# narsil.net
KiCad netlist of a schematic drawn in EAGLE
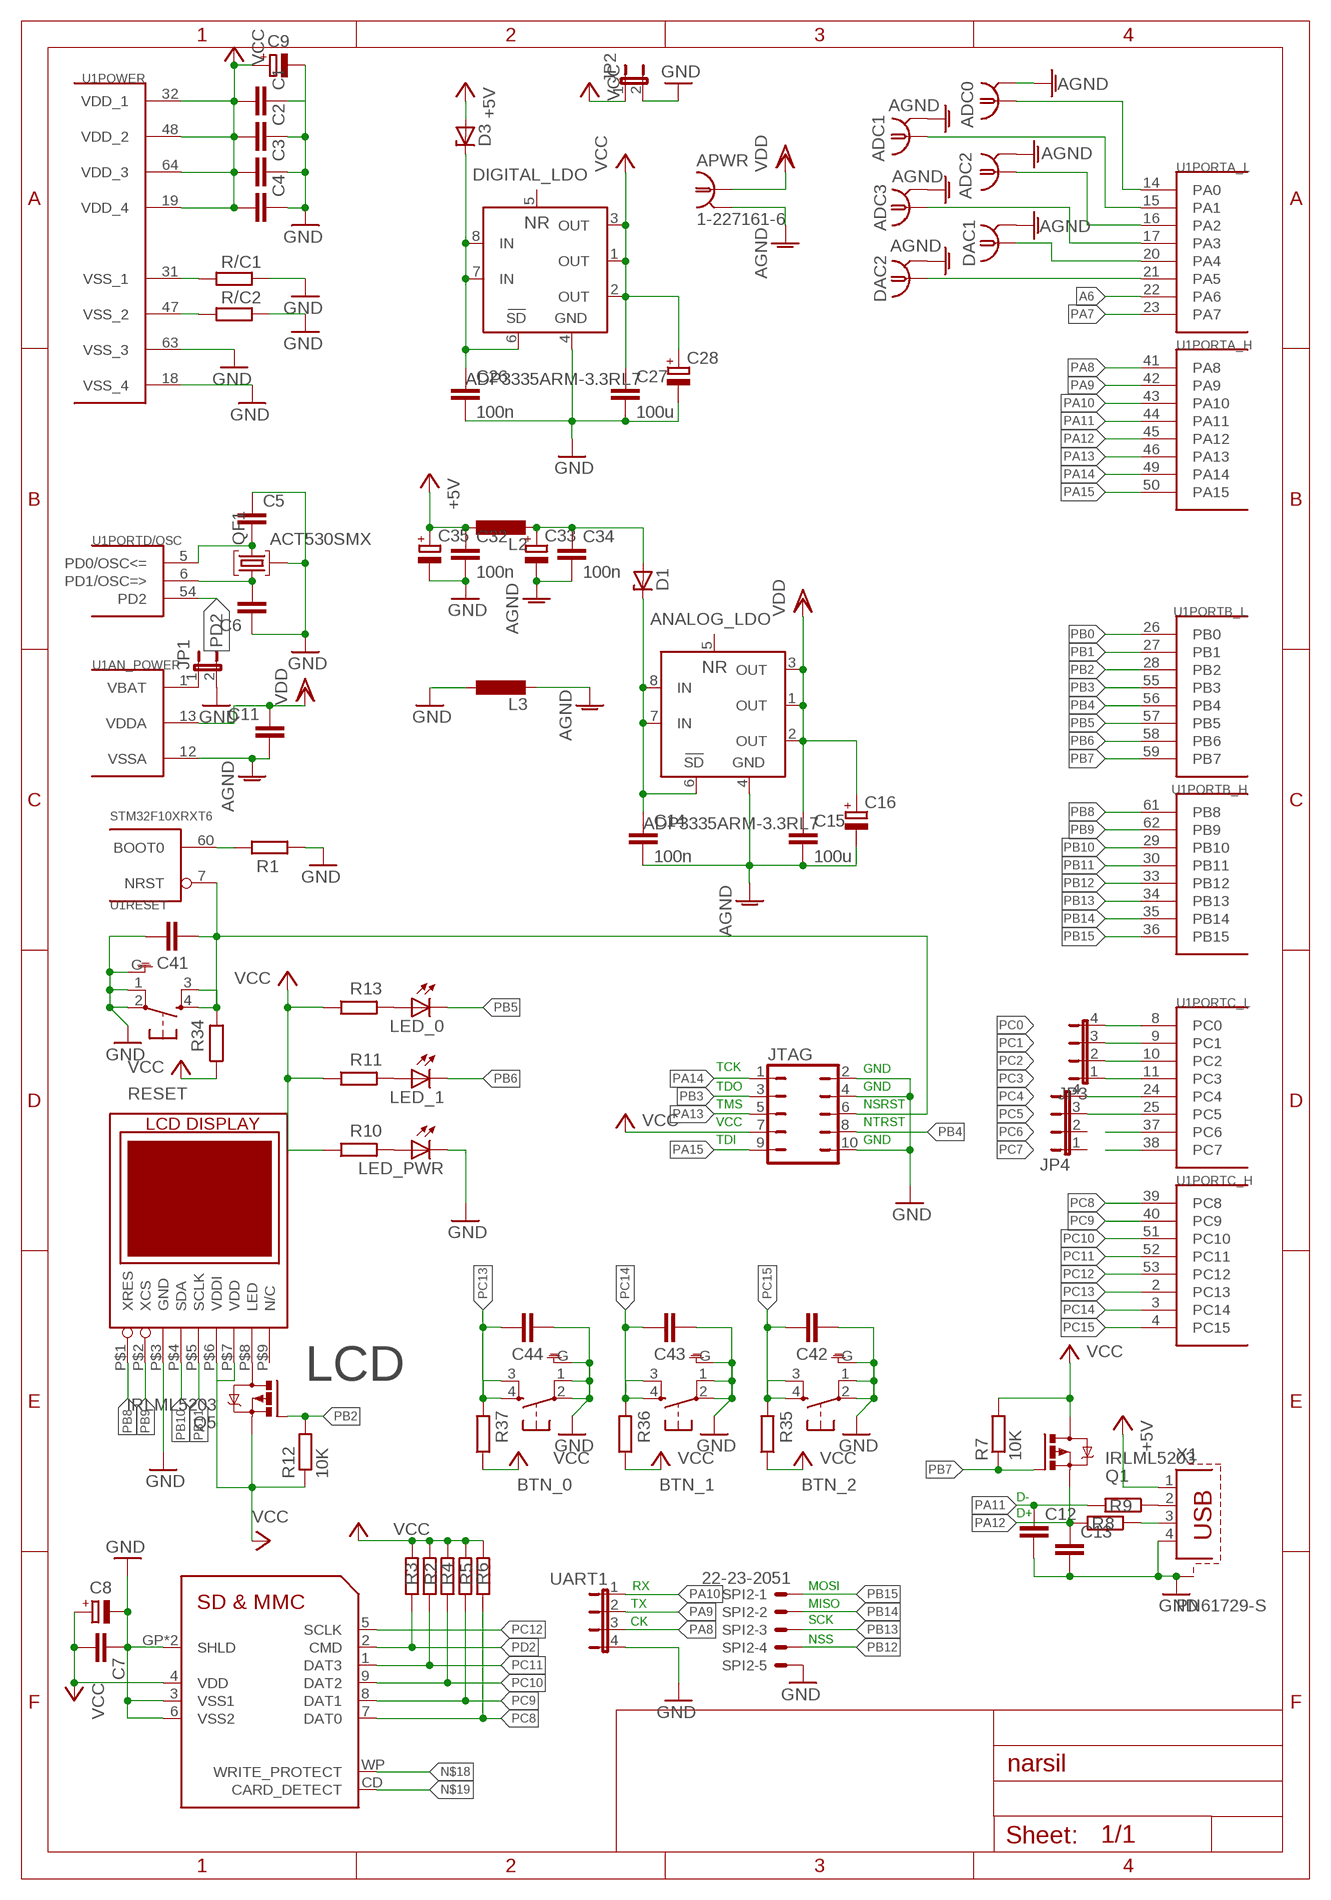
[diagram p0: schematic, sheet 1]

(export (version "E")
  (design (tool "Eeschema 10.0.6"))
  (components
    (comp (ref "ADC0")
      (value "1-227161-6")
      (footprint "eagle-import:AMP_227161")
      (fields (field (name "MF") "TYCO ELECTRONICS"))
      (libsource (lib "eagle-import") (part "?2271611--6"))
    )
    (comp (ref "ADC1")
      (value "1-227161-6")
      (footprint "eagle-import:AMP_227161")
      (fields (field (name "MF") "TYCO ELECTRONICS"))
      (libsource (lib "eagle-import") (part "?2271611--6"))
    )
    (comp (ref "ADC2")
      (value "1-227161-6")
      (footprint "eagle-import:AMP_227161")
      (fields (field (name "MF") "TYCO ELECTRONICS"))
      (libsource (lib "eagle-import") (part "?2271611--6"))
    )
    (comp (ref "ADC3")
      (value "1-227161-6")
      (footprint "eagle-import:AMP_227161")
      (fields
        (field (name "MF") "TYCO ELECTRONICS")
        (field (name "MF_1") "TYCO ELECTRONICS")
        (field (name "MPN") "1-227161-6")
        (field (name "OC_FARNELL") "unknown")
        (field (name "OC_NEWARK") "09H7854")
      )
      (libsource (lib "eagle-import") (part "?2271611--6"))
    )
    (comp (ref "ANALOG_LDO")
      (value "ADP3335ARM-3.3RL7")
      (footprint "eagle-import:MSOP08")
      (libsource (lib "eagle-import") (part "ADP3335ARM-3.3RL7"))
    )
    (comp (ref "APWR")
      (value "1-227161-6")
      (footprint "eagle-import:AMP_227161")
      (fields (field (name "MF") "TYCO ELECTRONICS"))
      (libsource (lib "eagle-import") (part "?2271611--6"))
    )
    (comp (ref "BTN_0")
      (value "10-XXG")
      (footprint "eagle-import:B3F-10XXG")
      (libsource (lib "eagle-import") (part "10-XXG"))
    )
    (comp (ref "BTN_1")
      (value "10-XXG")
      (footprint "eagle-import:B3F-10XXG")
      (libsource (lib "eagle-import") (part "10-XXG"))
    )
    (comp (ref "BTN_2")
      (value "10-XXG")
      (footprint "eagle-import:B3F-10XXG")
      (libsource (lib "eagle-import") (part "10-XXG"))
    )
    (comp (ref "C1")
      (value "C-EUC0805")
      (footprint "eagle-import:C0805")
      (libsource (lib "eagle-import") (part "resistor_C-EUC0805"))
    )
    (comp (ref "C2")
      (value "C-EUC0805")
      (footprint "eagle-import:C0805")
      (libsource (lib "eagle-import") (part "resistor_C-EUC0805"))
    )
    (comp (ref "C3")
      (value "C-EUC0805")
      (footprint "eagle-import:C0805")
      (libsource (lib "eagle-import") (part "resistor_C-EUC0805"))
    )
    (comp (ref "C4")
      (value "C-EUC0805")
      (footprint "eagle-import:C0805")
      (libsource (lib "eagle-import") (part "resistor_C-EUC0805"))
    )
    (comp (ref "C5")
      (value "C-EUC0805")
      (footprint "eagle-import:C0805")
      (libsource (lib "eagle-import") (part "resistor_C-EUC0805"))
    )
    (comp (ref "C6")
      (value "C-EUC0805")
      (footprint "eagle-import:C0805")
      (libsource (lib "eagle-import") (part "resistor_C-EUC0805"))
    )
    (comp (ref "C7")
      (value "C-EUC0805")
      (footprint "eagle-import:C0805")
      (libsource (lib "eagle-import") (part "resistor_C-EUC0805"))
    )
    (comp (ref "C8")
      (value "CPOL-EUSMCA")
      (footprint "eagle-import:SMC_A")
      (libsource (lib "eagle-import") (part "CPOL-EUSMCA"))
    )
    (comp (ref "C9")
      (value "CPOL-EUSMCA")
      (footprint "eagle-import:SMC_A")
      (libsource (lib "eagle-import") (part "CPOL-EUSMCA"))
    )
    (comp (ref "C11")
      (value "C-EUC0805")
      (footprint "eagle-import:C0805")
      (libsource (lib "eagle-import") (part "resistor_C-EUC0805"))
    )
    (comp (ref "C12")
      (value "C-EUC0805")
      (footprint "eagle-import:C0805")
      (libsource (lib "eagle-import") (part "resistor_C-EUC0805"))
    )
    (comp (ref "C13")
      (value "C-EUC0805")
      (footprint "eagle-import:C0805")
      (libsource (lib "eagle-import") (part "resistor_C-EUC0805"))
    )
    (comp (ref "C14")
      (value "100n")
      (footprint "eagle-import:C0805")
      (libsource (lib "eagle-import") (part "C-EUC0805"))
    )
    (comp (ref "C15")
      (value "100u")
      (footprint "eagle-import:C0805")
      (libsource (lib "eagle-import") (part "C-EUC0805"))
    )
    (comp (ref "C16")
      (value "CPOL-EUSMCA")
      (footprint "eagle-import:SMC_A")
      (libsource (lib "eagle-import") (part "CPOL-EUSMCA"))
    )
    (comp (ref "C26")
      (value "100n")
      (footprint "eagle-import:C0805")
      (libsource (lib "eagle-import") (part "C-EUC0805"))
    )
    (comp (ref "C27")
      (value "100u")
      (footprint "eagle-import:C0805")
      (libsource (lib "eagle-import") (part "C-EUC0805"))
    )
    (comp (ref "C28")
      (value "CPOL-EUSMCA")
      (footprint "eagle-import:SMC_A")
      (libsource (lib "eagle-import") (part "CPOL-EUSMCA"))
    )
    (comp (ref "C32")
      (value "100n")
      (footprint "eagle-import:C0805")
      (libsource (lib "eagle-import") (part "resistor_C-EUC0805"))
    )
    (comp (ref "C33")
      (value "CPOL-EUSMCA")
      (footprint "eagle-import:SMC_A")
      (libsource (lib "eagle-import") (part "CPOL-EUSMCA"))
    )
    (comp (ref "C34")
      (value "100n")
      (footprint "eagle-import:C0805")
      (libsource (lib "eagle-import") (part "resistor_C-EUC0805"))
    )
    (comp (ref "C35")
      (value "CPOL-EUSMCA")
      (footprint "eagle-import:SMC_A")
      (libsource (lib "eagle-import") (part "CPOL-EUSMCA"))
    )
    (comp (ref "C41")
      (value "C-EUC0805")
      (footprint "eagle-import:C0805")
      (libsource (lib "eagle-import") (part "resistor_C-EUC0805"))
    )
    (comp (ref "C42")
      (value "C-EUC0805")
      (footprint "eagle-import:C0805")
      (libsource (lib "eagle-import") (part "resistor_C-EUC0805"))
    )
    (comp (ref "C43")
      (value "C-EUC0805")
      (footprint "eagle-import:C0805")
      (libsource (lib "eagle-import") (part "resistor_C-EUC0805"))
    )
    (comp (ref "C44")
      (value "C-EUC0805")
      (footprint "eagle-import:C0805")
      (libsource (lib "eagle-import") (part "resistor_C-EUC0805"))
    )
    (comp (ref "D1")
      (value "ZENER-DIODESMB")
      (footprint "eagle-import:SMB")
      (libsource (lib "eagle-import") (part "ZENER-DIODESMB"))
    )
    (comp (ref "D3")
      (value "ZENER-DIODESMB")
      (footprint "eagle-import:SMB")
      (libsource (lib "eagle-import") (part "ZENER-DIODESMB"))
    )
    (comp (ref "DAC1")
      (value "1-227161-6")
      (footprint "eagle-import:AMP_227161")
      (fields (field (name "MF") "TYCO ELECTRONICS"))
      (libsource (lib "eagle-import") (part "?2271611--6"))
    )
    (comp (ref "DAC2")
      (value "1-227161-6")
      (footprint "eagle-import:AMP_227161")
      (fields (field (name "MF") "TYCO ELECTRONICS"))
      (libsource (lib "eagle-import") (part "?2271611--6"))
    )
    (comp (ref "DIGITAL_LDO")
      (value "ADP3335ARM-3.3RL7")
      (footprint "eagle-import:MSOP08")
      (libsource (lib "eagle-import") (part "ADP3335ARM-3.3RL7"))
    )
    (comp (ref "JP1")
      (value "JP1E")
      (footprint "eagle-import:JP1")
      (libsource (lib "eagle-import") (part "JP1E"))
    )
    (comp (ref "JP2")
      (value "JP1E")
      (footprint "eagle-import:JP1")
      (libsource (lib "eagle-import") (part "JP1E"))
    )
    (comp (ref "JP3")
      (value "JP4E")
      (footprint "eagle-import:JP4")
      (libsource (lib "eagle-import") (part "JP4E"))
    )
    (comp (ref "JP4")
      (value "JP4E")
      (footprint "eagle-import:JP4")
      (libsource (lib "eagle-import") (part "JP4E"))
    )
    (comp (ref "JTAG")
      (value "JP5Q")
      (footprint "eagle-import:JP5Q")
      (libsource (lib "eagle-import") (part "JP5Q"))
    )
    (comp (ref "L2")
      (value "L-EUL1206")
      (footprint "eagle-import:R1206")
      (libsource (lib "eagle-import") (part "L-EUL1206"))
    )
    (comp (ref "L3")
      (value "L-EUL1206")
      (footprint "eagle-import:R1206")
      (libsource (lib "eagle-import") (part "L-EUL1206"))
    )
    (comp (ref "LED_0")
      (value "LEDSMT1206")
      (footprint "eagle-import:1206")
      (libsource (lib "eagle-import") (part "LEDSMT1206"))
    )
    (comp (ref "LED_1")
      (value "LEDSMT1206")
      (footprint "eagle-import:1206")
      (libsource (lib "eagle-import") (part "LEDSMT1206"))
    )
    (comp (ref "LED_PWR")
      (value "LEDSMT1206")
      (footprint "eagle-import:1206")
      (libsource (lib "eagle-import") (part "LEDSMT1206"))
    )
    (comp (ref "Q1")
      (value "IRLML5203")
      (footprint "eagle-import:MICRO3")
      (libsource (lib "eagle-import") (part "IRLML5203"))
    )
    (comp (ref "Q5")
      (value "IRLML5203")
      (footprint "eagle-import:MICRO3")
      (libsource (lib "eagle-import") (part "IRLML5203"))
    )
    (comp (ref "QF1")
      (value "ACT530SMX")
      (footprint "eagle-import:ACT530SMX")
      (libsource (lib "eagle-import") (part "ACT530SMX"))
    )
    (comp (ref "R/C1")
      (value "R-EU_M0805")
      (footprint "eagle-import:M0805")
      (libsource (lib "eagle-import") (part "R-EU_M0805"))
    )
    (comp (ref "R/C2")
      (value "R-EU_M0805")
      (footprint "eagle-import:M0805")
      (libsource (lib "eagle-import") (part "R-EU_M0805"))
    )
    (comp (ref "R1")
      (value "5k")
      (footprint "eagle-import:M0805")
      (libsource (lib "eagle-import") (part "R-EU_M0805"))
    )
    (comp (ref "R2")
      (value "47k")
      (footprint "eagle-import:M0805")
      (libsource (lib "eagle-import") (part "R-EU_M0805"))
    )
    (comp (ref "R3")
      (value "47k")
      (footprint "eagle-import:M0805")
      (libsource (lib "eagle-import") (part "R-EU_M0805"))
    )
    (comp (ref "R4")
      (value "47k")
      (footprint "eagle-import:M0805")
      (libsource (lib "eagle-import") (part "R-EU_M0805"))
    )
    (comp (ref "R5")
      (value "47k")
      (footprint "eagle-import:M0805")
      (libsource (lib "eagle-import") (part "R-EU_M0805"))
    )
    (comp (ref "R6")
      (value "47k")
      (footprint "eagle-import:M0805")
      (libsource (lib "eagle-import") (part "R-EU_M0805"))
    )
    (comp (ref "R7")
      (value "10K")
      (footprint "eagle-import:M0805")
      (libsource (lib "eagle-import") (part "R-EU_M0805"))
    )
    (comp (ref "R8")
      (value "47k")
      (footprint "eagle-import:M0805")
      (libsource (lib "eagle-import") (part "R-EU_M0805"))
    )
    (comp (ref "R9")
      (value "47k")
      (footprint "eagle-import:M0805")
      (libsource (lib "eagle-import") (part "R-EU_M0805"))
    )
    (comp (ref "R10")
      (value "5k")
      (footprint "eagle-import:M0805")
      (libsource (lib "eagle-import") (part "R-EU_M0805"))
    )
    (comp (ref "R11")
      (value "5k")
      (footprint "eagle-import:M0805")
      (libsource (lib "eagle-import") (part "R-EU_M0805"))
    )
    (comp (ref "R12")
      (value "10K")
      (footprint "eagle-import:M0805")
      (libsource (lib "eagle-import") (part "R-EU_M0805"))
    )
    (comp (ref "R13")
      (value "5k")
      (footprint "eagle-import:M0805")
      (libsource (lib "eagle-import") (part "R-EU_M0805"))
    )
    (comp (ref "R34")
      (value "5k")
      (footprint "eagle-import:M0805")
      (libsource (lib "eagle-import") (part "R-EU_M0805"))
    )
    (comp (ref "R35")
      (value "5k")
      (footprint "eagle-import:M0805")
      (libsource (lib "eagle-import") (part "R-EU_M0805"))
    )
    (comp (ref "R36")
      (value "5k")
      (footprint "eagle-import:M0805")
      (libsource (lib "eagle-import") (part "R-EU_M0805"))
    )
    (comp (ref "R37")
      (value "5k")
      (footprint "eagle-import:M0805")
      (libsource (lib "eagle-import") (part "R-EU_M0805"))
    )
    (comp (ref "RESET")
      (value "10-XXG")
      (footprint "eagle-import:B3F-10XXG")
      (libsource (lib "eagle-import") (part "10-XXG"))
    )
    (comp (ref "SPI2")
      (value "22-23-2051")
      (footprint "eagle-import:22-23-2051")
      (fields (field (name "MF") "MOLEX"))
      (libsource (lib "eagle-import") (part "22-23-2051"))
    )
    (comp (ref "U$1")
      (value "SD-RSMT-2-MQ")
      (footprint "eagle-import:SD-RSMT-2-MQ")
      (libsource (lib "eagle-import") (part "SD-RSMT-2-MQ"))
    )
    (comp (ref "U$2")
      (value "LCD")
      (footprint "eagle-import:LCD_NOKIA1100")
      (libsource (lib "eagle-import") (part "LCD"))
    )
    (comp (ref "U1")
      (value "STM32F10XRXT6")
      (footprint "eagle-import:TQFP64")
      (libsource (lib "eagle-import") (part "STM32F10XRXT6"))
    )
    (comp (ref "UART1")
      (value "JP4E")
      (footprint "eagle-import:JP4")
      (libsource (lib "eagle-import") (part "JP4E"))
    )
    (comp (ref "X1")
      (value "PN61729-S")
      (footprint "eagle-import:PN61729-S")
      (libsource (lib "eagle-import") (part "PN61729-S"))
    )
  )
  (nets
    (net (code "1") (name "+5V") (class "Default")
      (node (ref "C32") (pin "1") (pinfunction "1_1") (pintype "passive"))
      (node (ref "C35") (pin "+") (pinfunction "+_+") (pintype "passive"))
      (node (ref "D3") (pin "A") (pinfunction "A_A") (pintype "passive"))
      (node (ref "L2") (pin "1") (pinfunction "1_1") (pintype "passive"))
      (node (ref "X1") (pin "1") (pinfunction "1_1") (pintype "passive"))
    )
    (net (code "2") (name "A6") (class "Default")
      (node (ref "U1") (pin "22") (pinfunction "PA6_22") (pintype "bidirectional"))
    )
    (net (code "3") (name "AGND") (class "Default")
      (node (ref "ADC0") (pin "2") (pinfunction "GND_2") (pintype "power_in"))
      (node (ref "ADC1") (pin "2") (pinfunction "GND_2") (pintype "power_in"))
      (node (ref "ADC2") (pin "2") (pinfunction "GND_2") (pintype "power_in"))
      (node (ref "ADC3") (pin "2") (pinfunction "GND_2") (pintype "power_in"))
      (node (ref "ANALOG_LDO") (pin "4") (pinfunction "GND_4") (pintype "power_in"))
      (node (ref "APWR") (pin "2") (pinfunction "GND_2") (pintype "power_in"))
      (node (ref "C11") (pin "2") (pinfunction "2_2") (pintype "passive"))
      (node (ref "C14") (pin "2") (pinfunction "2_2") (pintype "passive"))
      (node (ref "C15") (pin "2") (pinfunction "2_2") (pintype "passive"))
      (node (ref "C16") (pin "-") (pinfunction "-_-") (pintype "passive"))
      (node (ref "C33") (pin "-") (pinfunction "-_-") (pintype "passive"))
      (node (ref "C34") (pin "2") (pinfunction "2_2") (pintype "passive"))
      (node (ref "DAC1") (pin "2") (pinfunction "GND_2") (pintype "power_in"))
      (node (ref "DAC2") (pin "2") (pinfunction "GND_2") (pintype "power_in"))
      (node (ref "L3") (pin "2") (pinfunction "2_2") (pintype "passive"))
      (node (ref "U1") (pin "12") (pinfunction "VSSA_12") (pintype "power_in"))
    )
    (net (code "4") (name "GND") (class "Default")
      (node (ref "BTN_0") (pin "1") (pinfunction "P1_1") (pintype "passive"))
      (node (ref "BTN_0") (pin "2") (pinfunction "P_2") (pintype "passive"))
      (node (ref "BTN_0") (pin "G") (pinfunction "GND_G") (pintype "power_in"))
      (node (ref "BTN_1") (pin "1") (pinfunction "P1_1") (pintype "passive"))
      (node (ref "BTN_1") (pin "2") (pinfunction "P_2") (pintype "passive"))
      (node (ref "BTN_1") (pin "G") (pinfunction "GND_G") (pintype "power_in"))
      (node (ref "BTN_2") (pin "1") (pinfunction "P1_1") (pintype "passive"))
      (node (ref "BTN_2") (pin "2") (pinfunction "P_2") (pintype "passive"))
      (node (ref "BTN_2") (pin "G") (pinfunction "GND_G") (pintype "power_in"))
      (node (ref "C1") (pin "1") (pinfunction "1_1") (pintype "passive"))
      (node (ref "C12") (pin "2") (pinfunction "2_2") (pintype "passive"))
      (node (ref "C13") (pin "2") (pinfunction "2_2") (pintype "passive"))
      (node (ref "C2") (pin "1") (pinfunction "1_1") (pintype "passive"))
      (node (ref "C26") (pin "2") (pinfunction "2_2") (pintype "passive"))
      (node (ref "C27") (pin "2") (pinfunction "2_2") (pintype "passive"))
      (node (ref "C28") (pin "-") (pinfunction "-_-") (pintype "passive"))
      (node (ref "C3") (pin "1") (pinfunction "1_1") (pintype "passive"))
      (node (ref "C32") (pin "2") (pinfunction "2_2") (pintype "passive"))
      (node (ref "C35") (pin "-") (pinfunction "-_-") (pintype "passive"))
      (node (ref "C4") (pin "1") (pinfunction "1_1") (pintype "passive"))
      (node (ref "C41") (pin "1") (pinfunction "1_1") (pintype "passive"))
      (node (ref "C42") (pin "1") (pinfunction "1_1") (pintype "passive"))
      (node (ref "C43") (pin "1") (pinfunction "1_1") (pintype "passive"))
      (node (ref "C44") (pin "1") (pinfunction "1_1") (pintype "passive"))
      (node (ref "C5") (pin "1") (pinfunction "1_1") (pintype "passive"))
      (node (ref "C6") (pin "1") (pinfunction "1_1") (pintype "passive"))
      (node (ref "C7") (pin "1") (pinfunction "1_1") (pintype "passive"))
      (node (ref "C8") (pin "-") (pinfunction "-_-") (pintype "passive"))
      (node (ref "C9") (pin "-") (pinfunction "-_-") (pintype "passive"))
      (node (ref "DIGITAL_LDO") (pin "4") (pinfunction "GND_4") (pintype "power_in"))
      (node (ref "JP1") (pin "2") (pinfunction "2_2") (pintype "passive"))
      (node (ref "JP2") (pin "2") (pinfunction "2_2") (pintype "passive"))
      (node (ref "JTAG") (pin "10") (pinfunction "10_10") (pintype "passive"))
      (node (ref "JTAG") (pin "2") (pinfunction "2_2") (pintype "passive"))
      (node (ref "JTAG") (pin "4") (pinfunction "4_4") (pintype "passive"))
      (node (ref "L3") (pin "1") (pinfunction "1_1") (pintype "passive"))
      (node (ref "LED_PWR") (pin "C") (pinfunction "C_C") (pintype "passive"))
      (node (ref "QF1") (pin "S$1") (pinfunction "2_S$1") (pintype "passive"))
      (node (ref "QF1") (pin "S$2") (pinfunction "2_S$2") (pintype "passive"))
      (node (ref "R/C1") (pin "1") (pinfunction "1_1") (pintype "passive"))
      (node (ref "R/C2") (pin "1") (pinfunction "1_1") (pintype "passive"))
      (node (ref "R1") (pin "1") (pinfunction "1_1") (pintype "passive"))
      (node (ref "RESET") (pin "1") (pinfunction "P1_1") (pintype "passive"))
      (node (ref "RESET") (pin "2") (pinfunction "P_2") (pintype "passive"))
      (node (ref "RESET") (pin "G") (pinfunction "GND_G") (pintype "power_in"))
      (node (ref "SPI2") (pin "5") (pinfunction "S_5") (pintype "passive"))
      (node (ref "U$1") (pin "3") (pinfunction "VSS1_3") (pintype "power_in"))
      (node (ref "U$1") (pin "6") (pinfunction "VSS2_6") (pintype "power_in"))
      (node (ref "U$1") (pin "GP") (pinfunction "SHLD_GP") (pintype "power_in"))
      (node (ref "U$1") (pin "GP2") (pinfunction "SHLD_GP2") (pintype "power_in"))
      (node (ref "U$2") (pin "P$3") (pinfunction "GND_P$3") (pintype "power_in"))
      (node (ref "U1") (pin "18") (pinfunction "VSS_4_18") (pintype "power_in"))
      (node (ref "U1") (pin "63") (pinfunction "VSS_3_63") (pintype "power_in"))
      (node (ref "UART1") (pin "4") (pinfunction "4_4") (pintype "passive"))
      (node (ref "X1") (pin "4") (pinfunction "4_4") (pintype "passive"))
      (node (ref "X1") (pin "SHLD@1") (pinfunction "S1_SHLD@1") (pintype "passive"))
      (node (ref "X1") (pin "SHLD@2") (pinfunction "S1_SHLD@2") (pintype "passive"))
    )
    (net (code "5") (name "N$18") (class "Default")
      (node (ref "U$1") (pin "WP") (pinfunction "WRITE_PROTECT_WP") (pintype "passive"))
    )
    (net (code "6") (name "N$19") (class "Default")
      (node (ref "U$1") (pin "CD") (pinfunction "CARD_DETECT_CD") (pintype "passive"))
    )
    (net (code "7") (name "Net-(ANALOG_LDO-SD{slash})") (class "Default")
      (node (ref "ANALOG_LDO") (pin "6") (pinfunction "SD/_6") (pintype "input"))
      (node (ref "ANALOG_LDO") (pin "7") (pinfunction "IN_7") (pintype "input"))
      (node (ref "ANALOG_LDO") (pin "8") (pinfunction "IN_8") (pintype "input"))
      (node (ref "C14") (pin "1") (pinfunction "1_1") (pintype "passive"))
      (node (ref "D1") (pin "C") (pinfunction "C_C") (pintype "passive"))
    )
    (net (code "8") (name "Net-(C33-Pad+)") (class "Default")
      (node (ref "C33") (pin "+") (pinfunction "+_+") (pintype "passive"))
      (node (ref "C34") (pin "1") (pinfunction "1_1") (pintype "passive"))
      (node (ref "D1") (pin "A") (pinfunction "A_A") (pintype "passive"))
      (node (ref "L2") (pin "2") (pinfunction "2_2") (pintype "passive"))
    )
    (net (code "9") (name "Net-(DIGITAL_LDO-SD{slash})") (class "Default")
      (node (ref "C26") (pin "1") (pinfunction "1_1") (pintype "passive"))
      (node (ref "D3") (pin "C") (pinfunction "C_C") (pintype "passive"))
      (node (ref "DIGITAL_LDO") (pin "6") (pinfunction "SD/_6") (pintype "input"))
      (node (ref "DIGITAL_LDO") (pin "7") (pinfunction "IN_7") (pintype "input"))
      (node (ref "DIGITAL_LDO") (pin "8") (pinfunction "IN_8") (pintype "input"))
    )
    (net (code "10") (name "Net-(LED_0-PadA)") (class "Default")
      (node (ref "LED_0") (pin "A") (pinfunction "A_A") (pintype "passive"))
      (node (ref "R13") (pin "2") (pinfunction "2_2") (pintype "passive"))
    )
    (net (code "11") (name "Net-(LED_1-PadA)") (class "Default")
      (node (ref "LED_1") (pin "A") (pinfunction "A_A") (pintype "passive"))
      (node (ref "R11") (pin "2") (pinfunction "2_2") (pintype "passive"))
    )
    (net (code "12") (name "Net-(LED_PWR-PadA)") (class "Default")
      (node (ref "LED_PWR") (pin "A") (pinfunction "A_A") (pintype "passive"))
      (node (ref "R10") (pin "2") (pinfunction "2_2") (pintype "passive"))
    )
    (net (code "13") (name "Net-(Q5-D)") (class "Default")
      (node (ref "Q5") (pin "3") (pinfunction "D_3") (pintype "passive"))
      (node (ref "U$2") (pin "P$8") (pinfunction "LED_P$8") (pintype "power_in"))
    )
    (net (code "14") (name "Net-(QF1-1)") (class "Default")
      (node (ref "C6") (pin "2") (pinfunction "2_2") (pintype "passive"))
      (node (ref "QF1") (pin "P1") (pinfunction "1_P1") (pintype "passive"))
      (node (ref "U1") (pin "6") (pinfunction "PD1/OSC=>_6") (pintype "bidirectional"))
    )
    (net (code "15") (name "Net-(QF1-3)") (class "Default")
      (node (ref "C5") (pin "2") (pinfunction "2_2") (pintype "passive"))
      (node (ref "QF1") (pin "P2") (pinfunction "3_P2") (pintype "passive"))
      (node (ref "U1") (pin "5") (pinfunction "PD0/OSC<=_5") (pintype "bidirectional"))
    )
    (net (code "16") (name "Net-(R8-Pad1)") (class "Default")
      (node (ref "R8") (pin "1") (pinfunction "1_1") (pintype "passive"))
      (node (ref "X1") (pin "3") (pinfunction "3_3") (pintype "passive"))
    )
    (net (code "17") (name "Net-(R9-Pad1)") (class "Default")
      (node (ref "R9") (pin "1") (pinfunction "1_1") (pintype "passive"))
      (node (ref "X1") (pin "2") (pinfunction "2_2") (pintype "passive"))
    )
    (net (code "18") (name "Net-(RESET-S)") (class "Default")
      (node (ref "C41") (pin "2") (pinfunction "2_2") (pintype "passive"))
      (node (ref "JTAG") (pin "6") (pinfunction "6_6") (pintype "passive"))
      (node (ref "R34") (pin "2") (pinfunction "2_2") (pintype "passive"))
      (node (ref "RESET") (pin "3") (pinfunction "S1_3") (pintype "passive"))
      (node (ref "RESET") (pin "4") (pinfunction "S_4") (pintype "passive"))
      (node (ref "U1") (pin "7") (pinfunction "NRST_7") (pintype "input"))
    )
    (net (code "19") (name "Net-(U1A-VBAT)") (class "Default")
      (node (ref "JP1") (pin "1") (pinfunction "1_1") (pintype "passive"))
      (node (ref "U1") (pin "1") (pinfunction "VBAT_1") (pintype "power_in"))
    )
    (net (code "20") (name "Net-(U1C-PA0)") (class "Default")
      (node (ref "ADC0") (pin "1") (pinfunction "1_1") (pintype "passive"))
      (node (ref "U1") (pin "14") (pinfunction "PA0_14") (pintype "bidirectional"))
    )
    (net (code "21") (name "Net-(U1C-PA1)") (class "Default")
      (node (ref "ADC1") (pin "1") (pinfunction "1_1") (pintype "passive"))
      (node (ref "U1") (pin "15") (pinfunction "PA1_15") (pintype "bidirectional"))
    )
    (net (code "22") (name "Net-(U1C-PA2)") (class "Default")
      (node (ref "ADC2") (pin "1") (pinfunction "1_1") (pintype "passive"))
      (node (ref "U1") (pin "16") (pinfunction "PA2_16") (pintype "bidirectional"))
    )
    (net (code "23") (name "Net-(U1C-PA3)") (class "Default")
      (node (ref "ADC3") (pin "1") (pinfunction "1_1") (pintype "passive"))
      (node (ref "U1") (pin "17") (pinfunction "PA3_17") (pintype "bidirectional"))
    )
    (net (code "24") (name "Net-(U1C-PA4)") (class "Default")
      (node (ref "DAC1") (pin "1") (pinfunction "1_1") (pintype "passive"))
      (node (ref "U1") (pin "20") (pinfunction "PA4_20") (pintype "bidirectional"))
    )
    (net (code "25") (name "Net-(U1C-PA5)") (class "Default")
      (node (ref "DAC2") (pin "1") (pinfunction "1_1") (pintype "passive"))
      (node (ref "U1") (pin "21") (pinfunction "PA5_21") (pintype "bidirectional"))
    )
    (net (code "26") (name "Net-(U1I-VSS_1)") (class "Default")
      (node (ref "R/C1") (pin "2") (pinfunction "2_2") (pintype "passive"))
      (node (ref "U1") (pin "31") (pinfunction "VSS_1_31") (pintype "power_in"))
    )
    (net (code "27") (name "Net-(U1I-VSS_2)") (class "Default")
      (node (ref "R/C2") (pin "2") (pinfunction "2_2") (pintype "passive"))
      (node (ref "U1") (pin "47") (pinfunction "VSS_2_47") (pintype "power_in"))
    )
    (net (code "28") (name "Net-(U1J-BOOT0)") (class "Default")
      (node (ref "R1") (pin "2") (pinfunction "2_2") (pintype "passive"))
      (node (ref "U1") (pin "60") (pinfunction "BOOT0_60") (pintype "input"))
    )
    (net (code "29") (name "PA7") (class "Default")
      (node (ref "U1") (pin "23") (pinfunction "PA7_23") (pintype "bidirectional"))
    )
    (net (code "30") (name "PA8") (class "Default")
      (node (ref "U1") (pin "41") (pinfunction "PA8_41") (pintype "bidirectional"))
      (node (ref "UART1") (pin "3") (pinfunction "3_3") (pintype "passive"))
    )
    (net (code "31") (name "PA9") (class "Default")
      (node (ref "U1") (pin "42") (pinfunction "PA9_42") (pintype "bidirectional"))
      (node (ref "UART1") (pin "2") (pinfunction "2_2") (pintype "passive"))
    )
    (net (code "32") (name "PA10") (class "Default")
      (node (ref "U1") (pin "43") (pinfunction "PA10_43") (pintype "bidirectional"))
      (node (ref "UART1") (pin "1") (pinfunction "1_1") (pintype "passive"))
    )
    (net (code "33") (name "PA11") (class "Default")
      (node (ref "C12") (pin "1") (pinfunction "1_1") (pintype "passive"))
      (node (ref "R9") (pin "2") (pinfunction "2_2") (pintype "passive"))
      (node (ref "U1") (pin "44") (pinfunction "PA11_44") (pintype "bidirectional"))
    )
    (net (code "34") (name "PA12") (class "Default")
      (node (ref "C13") (pin "1") (pinfunction "1_1") (pintype "passive"))
      (node (ref "Q1") (pin "2") (pinfunction "S_2") (pintype "passive"))
      (node (ref "R8") (pin "2") (pinfunction "2_2") (pintype "passive"))
      (node (ref "U1") (pin "45") (pinfunction "PA12_45") (pintype "bidirectional"))
    )
    (net (code "35") (name "PA13") (class "Default")
      (node (ref "JTAG") (pin "5") (pinfunction "5_5") (pintype "passive"))
      (node (ref "U1") (pin "46") (pinfunction "PA13_46") (pintype "bidirectional"))
    )
    (net (code "36") (name "PA14") (class "Default")
      (node (ref "JTAG") (pin "1") (pinfunction "1_1") (pintype "passive"))
      (node (ref "U1") (pin "49") (pinfunction "PA14_49") (pintype "bidirectional"))
    )
    (net (code "37") (name "PA15") (class "Default")
      (node (ref "JTAG") (pin "9") (pinfunction "9_9") (pintype "passive"))
      (node (ref "U1") (pin "50") (pinfunction "PA15_50") (pintype "bidirectional"))
    )
    (net (code "38") (name "PB0") (class "Default")
      (node (ref "U1") (pin "26") (pinfunction "PB0_26") (pintype "bidirectional"))
    )
    (net (code "39") (name "PB1") (class "Default")
      (node (ref "U1") (pin "27") (pinfunction "PB1_27") (pintype "bidirectional"))
    )
    (net (code "40") (name "PB2") (class "Default")
      (node (ref "Q5") (pin "1") (pinfunction "G_1") (pintype "passive"))
      (node (ref "R12") (pin "2") (pinfunction "2_2") (pintype "passive"))
      (node (ref "U1") (pin "28") (pinfunction "PB2_28") (pintype "bidirectional"))
    )
    (net (code "41") (name "PB3") (class "Default")
      (node (ref "JTAG") (pin "3") (pinfunction "3_3") (pintype "passive"))
      (node (ref "U1") (pin "55") (pinfunction "PB3_55") (pintype "bidirectional"))
    )
    (net (code "42") (name "PB4") (class "Default")
      (node (ref "JTAG") (pin "8") (pinfunction "8_8") (pintype "passive"))
      (node (ref "U1") (pin "56") (pinfunction "PB4_56") (pintype "bidirectional"))
    )
    (net (code "43") (name "PB5") (class "Default")
      (node (ref "LED_0") (pin "C") (pinfunction "C_C") (pintype "passive"))
      (node (ref "U1") (pin "57") (pinfunction "PB5_57") (pintype "bidirectional"))
    )
    (net (code "44") (name "PB6") (class "Default")
      (node (ref "LED_1") (pin "C") (pinfunction "C_C") (pintype "passive"))
      (node (ref "U1") (pin "58") (pinfunction "PB6_58") (pintype "bidirectional"))
    )
    (net (code "45") (name "PB7") (class "Default")
      (node (ref "Q1") (pin "1") (pinfunction "G_1") (pintype "passive"))
      (node (ref "R7") (pin "1") (pinfunction "1_1") (pintype "passive"))
      (node (ref "U1") (pin "59") (pinfunction "PB7_59") (pintype "bidirectional"))
    )
    (net (code "46") (name "PB8") (class "Default")
      (node (ref "U$2") (pin "P$1") (pinfunction "XRES_P$1") (pintype "input"))
      (node (ref "U1") (pin "61") (pinfunction "PB8_61") (pintype "bidirectional"))
    )
    (net (code "47") (name "PB9") (class "Default")
      (node (ref "U$2") (pin "P$2") (pinfunction "XCS_P$2") (pintype "input"))
      (node (ref "U1") (pin "62") (pinfunction "PB9_62") (pintype "bidirectional"))
    )
    (net (code "48") (name "PB10") (class "Default")
      (node (ref "U$2") (pin "P$4") (pinfunction "SDA_P$4") (pintype "input"))
      (node (ref "U1") (pin "29") (pinfunction "PB10_29") (pintype "bidirectional"))
    )
    (net (code "49") (name "PB11") (class "Default")
      (node (ref "U$2") (pin "P$5") (pinfunction "SCLK_P$5") (pintype "input"))
      (node (ref "U1") (pin "30") (pinfunction "PB11_30") (pintype "bidirectional"))
    )
    (net (code "50") (name "PB12") (class "Default")
      (node (ref "SPI2") (pin "4") (pinfunction "S_4") (pintype "passive"))
      (node (ref "U1") (pin "33") (pinfunction "PB12_33") (pintype "bidirectional"))
    )
    (net (code "51") (name "PB13") (class "Default")
      (node (ref "SPI2") (pin "3") (pinfunction "S_3") (pintype "passive"))
      (node (ref "U1") (pin "34") (pinfunction "PB13_34") (pintype "bidirectional"))
    )
    (net (code "52") (name "PB14") (class "Default")
      (node (ref "SPI2") (pin "2") (pinfunction "S_2") (pintype "passive"))
      (node (ref "U1") (pin "35") (pinfunction "PB14_35") (pintype "bidirectional"))
    )
    (net (code "53") (name "PB15") (class "Default")
      (node (ref "SPI2") (pin "1") (pinfunction "S_1") (pintype "passive"))
      (node (ref "U1") (pin "36") (pinfunction "PB15_36") (pintype "bidirectional"))
    )
    (net (code "54") (name "PC0") (class "Default")
      (node (ref "JP3") (pin "4") (pinfunction "4_4") (pintype "passive"))
      (node (ref "U1") (pin "8") (pinfunction "PC0_8") (pintype "bidirectional"))
    )
    (net (code "55") (name "PC1") (class "Default")
      (node (ref "JP3") (pin "3") (pinfunction "3_3") (pintype "passive"))
      (node (ref "U1") (pin "9") (pinfunction "PC1_9") (pintype "bidirectional"))
    )
    (net (code "56") (name "PC2") (class "Default")
      (node (ref "JP3") (pin "2") (pinfunction "2_2") (pintype "passive"))
      (node (ref "U1") (pin "10") (pinfunction "PC2_10") (pintype "bidirectional"))
    )
    (net (code "57") (name "PC3") (class "Default")
      (node (ref "JP3") (pin "1") (pinfunction "1_1") (pintype "passive"))
      (node (ref "U1") (pin "11") (pinfunction "PC3_11") (pintype "bidirectional"))
    )
    (net (code "58") (name "PC4") (class "Default")
      (node (ref "JP4") (pin "4") (pinfunction "4_4") (pintype "passive"))
      (node (ref "U1") (pin "24") (pinfunction "PC4_24") (pintype "bidirectional"))
    )
    (net (code "59") (name "PC5") (class "Default")
      (node (ref "JP4") (pin "3") (pinfunction "3_3") (pintype "passive"))
      (node (ref "U1") (pin "25") (pinfunction "PC5_25") (pintype "bidirectional"))
    )
    (net (code "60") (name "PC6") (class "Default")
      (node (ref "U1") (pin "37") (pinfunction "PC6_37") (pintype "bidirectional"))
    )
    (net (code "61") (name "PC7") (class "Default")
      (node (ref "U1") (pin "38") (pinfunction "PC7_38") (pintype "bidirectional"))
    )
    (net (code "62") (name "PC8") (class "Default")
      (node (ref "R6") (pin "1") (pinfunction "1_1") (pintype "passive"))
      (node (ref "U$1") (pin "7") (pinfunction "DAT0_7") (pintype "output"))
      (node (ref "U1") (pin "39") (pinfunction "PC8_39") (pintype "bidirectional"))
    )
    (net (code "63") (name "PC9") (class "Default")
      (node (ref "R5") (pin "1") (pinfunction "1_1") (pintype "passive"))
      (node (ref "U$1") (pin "8") (pinfunction "DAT1_8") (pintype "bidirectional"))
      (node (ref "U1") (pin "40") (pinfunction "PC9_40") (pintype "bidirectional"))
    )
    (net (code "64") (name "PC10") (class "Default")
      (node (ref "R4") (pin "1") (pinfunction "1_1") (pintype "passive"))
      (node (ref "U$1") (pin "9") (pinfunction "DAT2_9") (pintype "bidirectional"))
      (node (ref "U1") (pin "51") (pinfunction "PC10_51") (pintype "bidirectional"))
    )
    (net (code "65") (name "PC11") (class "Default")
      (node (ref "R2") (pin "1") (pinfunction "1_1") (pintype "passive"))
      (node (ref "U$1") (pin "1") (pinfunction "DAT3_1") (pintype "input"))
      (node (ref "U1") (pin "52") (pinfunction "PC11_52") (pintype "bidirectional"))
    )
    (net (code "66") (name "PC12") (class "Default")
      (node (ref "U$1") (pin "5") (pinfunction "SCLK_5") (pintype "input"))
      (node (ref "U1") (pin "53") (pinfunction "PC12_53") (pintype "bidirectional"))
    )
    (net (code "67") (name "PC13") (class "Default")
      (node (ref "BTN_0") (pin "3") (pinfunction "S1_3") (pintype "passive"))
      (node (ref "BTN_0") (pin "4") (pinfunction "S_4") (pintype "passive"))
      (node (ref "C44") (pin "2") (pinfunction "2_2") (pintype "passive"))
      (node (ref "R37") (pin "2") (pinfunction "2_2") (pintype "passive"))
      (node (ref "U1") (pin "2") (pinfunction "PC13_2") (pintype "bidirectional"))
    )
    (net (code "68") (name "PC14") (class "Default")
      (node (ref "BTN_1") (pin "3") (pinfunction "S1_3") (pintype "passive"))
      (node (ref "BTN_1") (pin "4") (pinfunction "S_4") (pintype "passive"))
      (node (ref "C43") (pin "2") (pinfunction "2_2") (pintype "passive"))
      (node (ref "R36") (pin "2") (pinfunction "2_2") (pintype "passive"))
      (node (ref "U1") (pin "3") (pinfunction "PC14_3") (pintype "bidirectional"))
    )
    (net (code "69") (name "PC15") (class "Default")
      (node (ref "BTN_2") (pin "3") (pinfunction "S1_3") (pintype "passive"))
      (node (ref "BTN_2") (pin "4") (pinfunction "S_4") (pintype "passive"))
      (node (ref "C42") (pin "2") (pinfunction "2_2") (pintype "passive"))
      (node (ref "R35") (pin "2") (pinfunction "2_2") (pintype "passive"))
      (node (ref "U1") (pin "4") (pinfunction "PC15_4") (pintype "bidirectional"))
    )
    (net (code "70") (name "PD2") (class "Default")
      (node (ref "R3") (pin "1") (pinfunction "1_1") (pintype "passive"))
      (node (ref "U$1") (pin "2") (pinfunction "CMD_2") (pintype "input"))
      (node (ref "U1") (pin "54") (pinfunction "PD2_54") (pintype "bidirectional"))
    )
    (net (code "71") (name "VCC") (class "Default")
      (node (ref "C1") (pin "2") (pinfunction "2_2") (pintype "passive"))
      (node (ref "C2") (pin "2") (pinfunction "2_2") (pintype "passive"))
      (node (ref "C27") (pin "1") (pinfunction "1_1") (pintype "passive"))
      (node (ref "C28") (pin "+") (pinfunction "+_+") (pintype "passive"))
      (node (ref "C3") (pin "2") (pinfunction "2_2") (pintype "passive"))
      (node (ref "C4") (pin "2") (pinfunction "2_2") (pintype "passive"))
      (node (ref "C7") (pin "2") (pinfunction "2_2") (pintype "passive"))
      (node (ref "C8") (pin "+") (pinfunction "+_+") (pintype "passive"))
      (node (ref "C9") (pin "+") (pinfunction "+_+") (pintype "passive"))
      (node (ref "DIGITAL_LDO") (pin "1") (pinfunction "OUT_1") (pintype "passive"))
      (node (ref "DIGITAL_LDO") (pin "2") (pinfunction "OUT_2") (pintype "passive"))
      (node (ref "DIGITAL_LDO") (pin "3") (pinfunction "OUT_3") (pintype "passive"))
      (node (ref "JP2") (pin "1") (pinfunction "1_1") (pintype "passive"))
      (node (ref "JTAG") (pin "7") (pinfunction "7_7") (pintype "passive"))
      (node (ref "Q1") (pin "3") (pinfunction "D_3") (pintype "passive"))
      (node (ref "Q5") (pin "2") (pinfunction "S_2") (pintype "passive"))
      (node (ref "R10") (pin "1") (pinfunction "1_1") (pintype "passive"))
      (node (ref "R11") (pin "1") (pinfunction "1_1") (pintype "passive"))
      (node (ref "R12") (pin "1") (pinfunction "1_1") (pintype "passive"))
      (node (ref "R13") (pin "1") (pinfunction "1_1") (pintype "passive"))
      (node (ref "R2") (pin "2") (pinfunction "2_2") (pintype "passive"))
      (node (ref "R3") (pin "2") (pinfunction "2_2") (pintype "passive"))
      (node (ref "R34") (pin "1") (pinfunction "1_1") (pintype "passive"))
      (node (ref "R35") (pin "1") (pinfunction "1_1") (pintype "passive"))
      (node (ref "R36") (pin "1") (pinfunction "1_1") (pintype "passive"))
      (node (ref "R37") (pin "1") (pinfunction "1_1") (pintype "passive"))
      (node (ref "R4") (pin "2") (pinfunction "2_2") (pintype "passive"))
      (node (ref "R5") (pin "2") (pinfunction "2_2") (pintype "passive"))
      (node (ref "R6") (pin "2") (pinfunction "2_2") (pintype "passive"))
      (node (ref "R7") (pin "2") (pinfunction "2_2") (pintype "passive"))
      (node (ref "U$1") (pin "4") (pinfunction "VDD_4") (pintype "power_in"))
      (node (ref "U$2") (pin "P$6") (pinfunction "VDDI_P$6") (pintype "power_in"))
      (node (ref "U$2") (pin "P$7") (pinfunction "VDD_P$7") (pintype "power_in"))
      (node (ref "U1") (pin "19") (pinfunction "VDD_4_19") (pintype "power_in"))
      (node (ref "U1") (pin "32") (pinfunction "VDD_1_32") (pintype "power_in"))
      (node (ref "U1") (pin "48") (pinfunction "VDD_2_48") (pintype "power_in"))
      (node (ref "U1") (pin "64") (pinfunction "VDD_3_64") (pintype "power_in"))
    )
    (net (code "72") (name "VDD") (class "Default")
      (node (ref "ANALOG_LDO") (pin "1") (pinfunction "OUT_1") (pintype "passive"))
      (node (ref "ANALOG_LDO") (pin "2") (pinfunction "OUT_2") (pintype "passive"))
      (node (ref "ANALOG_LDO") (pin "3") (pinfunction "OUT_3") (pintype "passive"))
      (node (ref "APWR") (pin "1") (pinfunction "1_1") (pintype "passive"))
      (node (ref "C11") (pin "1") (pinfunction "1_1") (pintype "passive"))
      (node (ref "C15") (pin "1") (pinfunction "1_1") (pintype "passive"))
      (node (ref "C16") (pin "+") (pinfunction "+_+") (pintype "passive"))
      (node (ref "U1") (pin "13") (pinfunction "VDDA_13") (pintype "power_in"))
    )
    (net (code "73") (name "unconnected-(ANALOG_LDO-NR-Pad5)") (class "Default")
      (node (ref "ANALOG_LDO") (pin "5") (pinfunction "NR_5") (pintype "passive"))
    )
    (net (code "74") (name "unconnected-(DIGITAL_LDO-NR-Pad5)") (class "Default")
      (node (ref "DIGITAL_LDO") (pin "5") (pinfunction "NR_5") (pintype "passive"))
    )
    (net (code "75") (name "unconnected-(JP4-Pad1)") (class "Default")
      (node (ref "JP4") (pin "1") (pinfunction "1_1") (pintype "passive"))
    )
    (net (code "76") (name "unconnected-(JP4-Pad2)") (class "Default")
      (node (ref "JP4") (pin "2") (pinfunction "2_2") (pintype "passive"))
    )
    (net (code "77") (name "unconnected-(U$2-N{slash}C-PadP$9)") (class "Default")
      (node (ref "U$2") (pin "P$9") (pinfunction "N/C_P$9") (pintype "no_connect"))
    )
  )
)
